# main.net
KiCad netlist of a schematic drawn in EAGLE
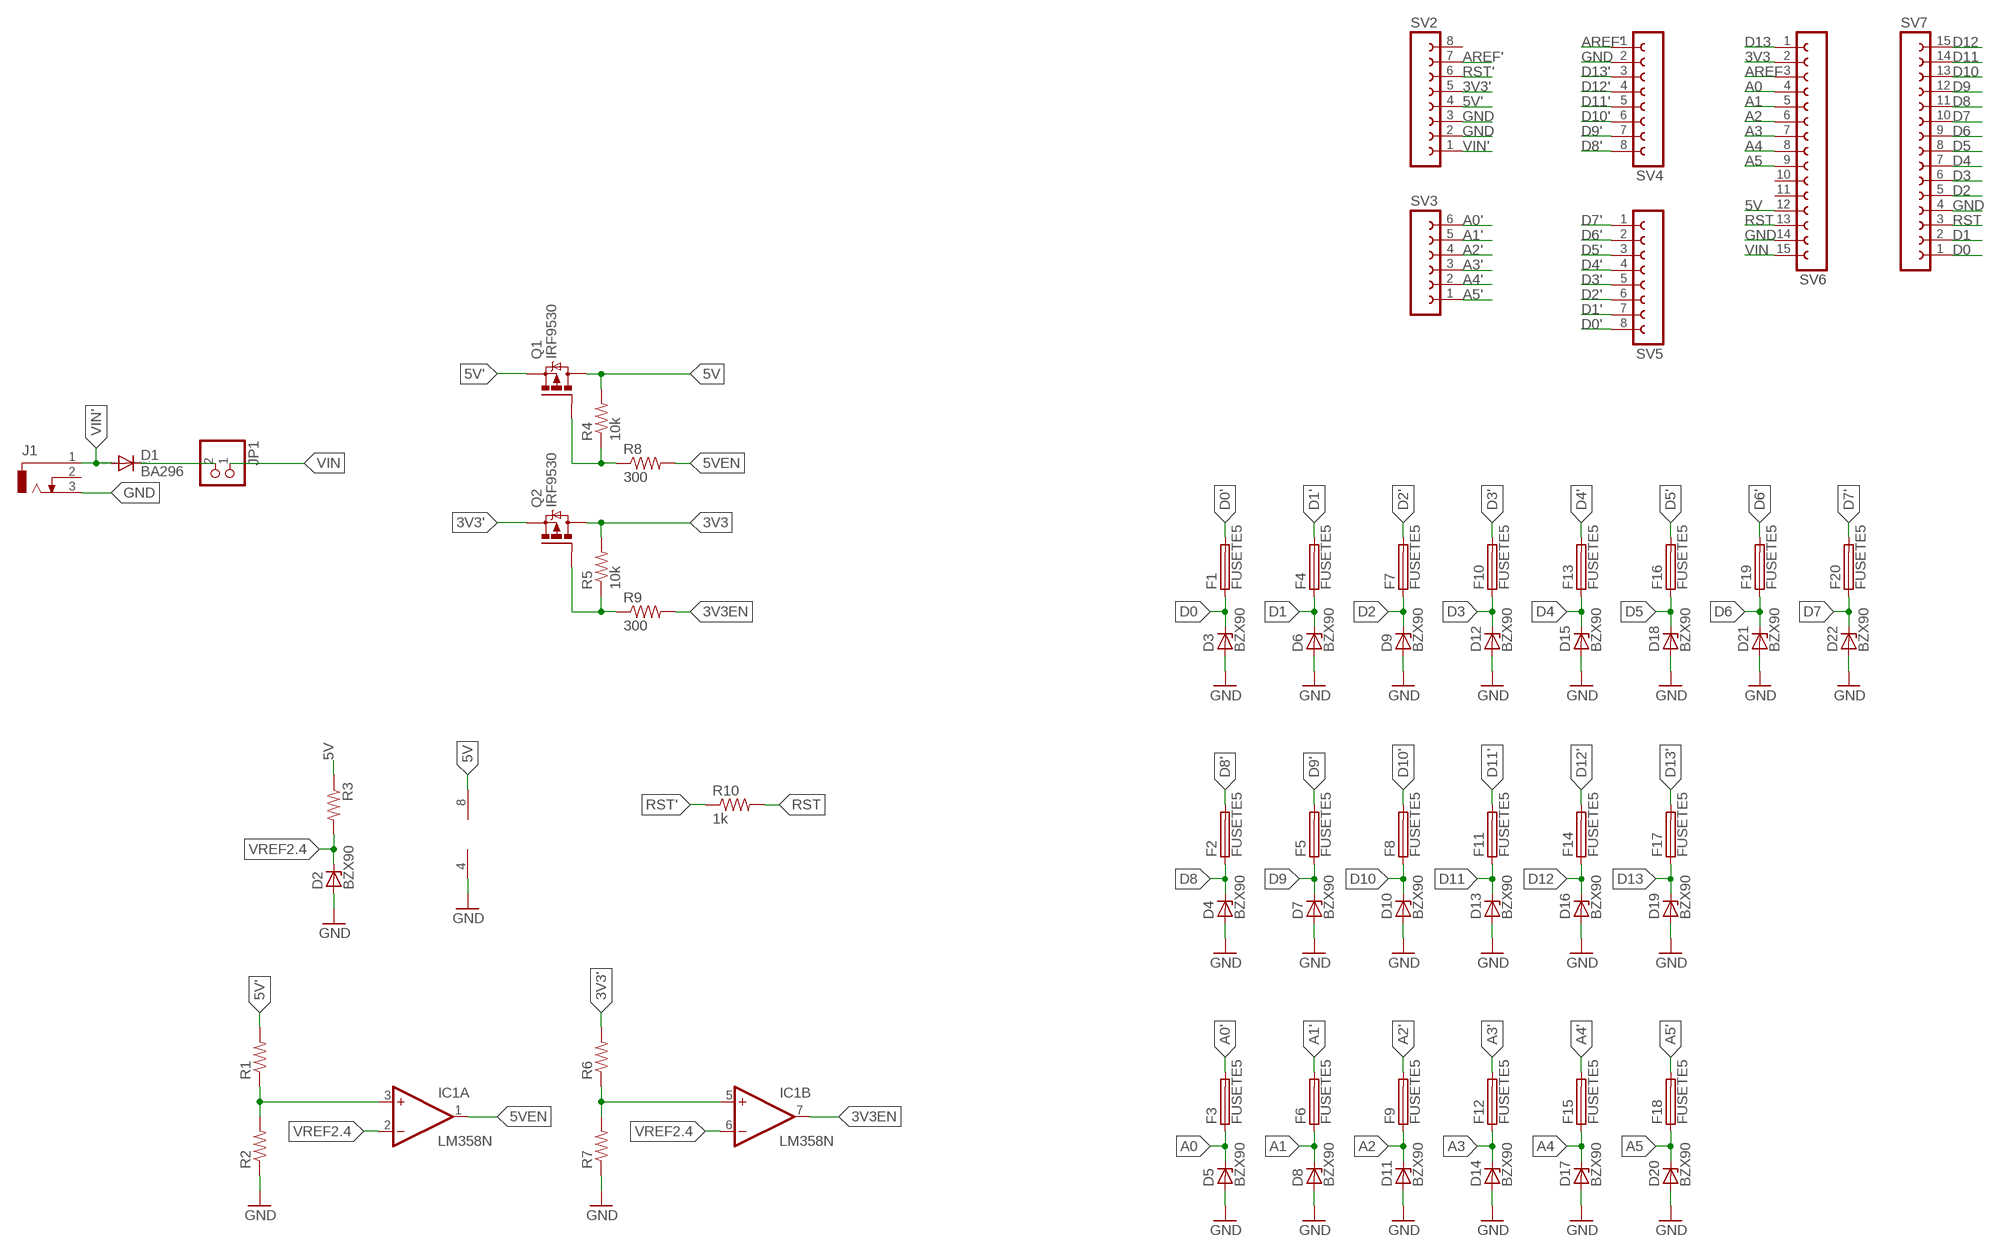
[diagram p0: schematic, sheet 1]

(export (version "E")
  (design (tool "Eeschema 10.0.6"))
  (components
    (comp (ref "D1")
      (value "BA296")
      (footprint "eagle-import:P2-15")
      (libsource (lib "eagle-import") (part "BA296"))
    )
    (comp (ref "D2")
      (value "BZX90")
      (footprint "eagle-import:DO34Z7")
      (libsource (lib "eagle-import") (part "BZX90"))
    )
    (comp (ref "D3")
      (value "BZX90")
      (footprint "eagle-import:DO34Z7")
      (libsource (lib "eagle-import") (part "BZX90"))
    )
    (comp (ref "D4")
      (value "BZX90")
      (footprint "eagle-import:DO34Z7")
      (libsource (lib "eagle-import") (part "BZX90"))
    )
    (comp (ref "D5")
      (value "BZX90")
      (footprint "eagle-import:DO34Z7")
      (libsource (lib "eagle-import") (part "BZX90"))
    )
    (comp (ref "D6")
      (value "BZX90")
      (footprint "eagle-import:DO34Z7")
      (libsource (lib "eagle-import") (part "BZX90"))
    )
    (comp (ref "D7")
      (value "BZX90")
      (footprint "eagle-import:DO34Z7")
      (libsource (lib "eagle-import") (part "BZX90"))
    )
    (comp (ref "D8")
      (value "BZX90")
      (footprint "eagle-import:DO34Z7")
      (libsource (lib "eagle-import") (part "BZX90"))
    )
    (comp (ref "D9")
      (value "BZX90")
      (footprint "eagle-import:DO34Z7")
      (libsource (lib "eagle-import") (part "BZX90"))
    )
    (comp (ref "D10")
      (value "BZX90")
      (footprint "eagle-import:DO34Z7")
      (libsource (lib "eagle-import") (part "BZX90"))
    )
    (comp (ref "D11")
      (value "BZX90")
      (footprint "eagle-import:DO34Z7")
      (libsource (lib "eagle-import") (part "BZX90"))
    )
    (comp (ref "D12")
      (value "BZX90")
      (footprint "eagle-import:DO34Z7")
      (libsource (lib "eagle-import") (part "BZX90"))
    )
    (comp (ref "D13")
      (value "BZX90")
      (footprint "eagle-import:DO34Z7")
      (libsource (lib "eagle-import") (part "BZX90"))
    )
    (comp (ref "D14")
      (value "BZX90")
      (footprint "eagle-import:DO34Z7")
      (libsource (lib "eagle-import") (part "BZX90"))
    )
    (comp (ref "D15")
      (value "BZX90")
      (footprint "eagle-import:DO34Z7")
      (libsource (lib "eagle-import") (part "BZX90"))
    )
    (comp (ref "D16")
      (value "BZX90")
      (footprint "eagle-import:DO34Z7")
      (libsource (lib "eagle-import") (part "BZX90"))
    )
    (comp (ref "D17")
      (value "BZX90")
      (footprint "eagle-import:DO34Z7")
      (libsource (lib "eagle-import") (part "BZX90"))
    )
    (comp (ref "D18")
      (value "BZX90")
      (footprint "eagle-import:DO34Z7")
      (libsource (lib "eagle-import") (part "BZX90"))
    )
    (comp (ref "D19")
      (value "BZX90")
      (footprint "eagle-import:DO34Z7")
      (libsource (lib "eagle-import") (part "BZX90"))
    )
    (comp (ref "D20")
      (value "BZX90")
      (footprint "eagle-import:DO34Z7")
      (libsource (lib "eagle-import") (part "BZX90"))
    )
    (comp (ref "D21")
      (value "BZX90")
      (footprint "eagle-import:DO34Z7")
      (libsource (lib "eagle-import") (part "BZX90"))
    )
    (comp (ref "D22")
      (value "BZX90")
      (footprint "eagle-import:DO34Z7")
      (libsource (lib "eagle-import") (part "BZX90"))
    )
    (comp (ref "F1")
      (value "FUSETE5")
      (footprint "eagle-import:TE5")
      (libsource (lib "eagle-import") (part "FUSETE5"))
    )
    (comp (ref "F2")
      (value "FUSETE5")
      (footprint "eagle-import:TE5")
      (libsource (lib "eagle-import") (part "FUSETE5"))
    )
    (comp (ref "F3")
      (value "FUSETE5")
      (footprint "eagle-import:TE5")
      (libsource (lib "eagle-import") (part "FUSETE5"))
    )
    (comp (ref "F4")
      (value "FUSETE5")
      (footprint "eagle-import:TE5")
      (libsource (lib "eagle-import") (part "FUSETE5"))
    )
    (comp (ref "F5")
      (value "FUSETE5")
      (footprint "eagle-import:TE5")
      (libsource (lib "eagle-import") (part "FUSETE5"))
    )
    (comp (ref "F6")
      (value "FUSETE5")
      (footprint "eagle-import:TE5")
      (libsource (lib "eagle-import") (part "FUSETE5"))
    )
    (comp (ref "F7")
      (value "FUSETE5")
      (footprint "eagle-import:TE5")
      (libsource (lib "eagle-import") (part "FUSETE5"))
    )
    (comp (ref "F8")
      (value "FUSETE5")
      (footprint "eagle-import:TE5")
      (libsource (lib "eagle-import") (part "FUSETE5"))
    )
    (comp (ref "F9")
      (value "FUSETE5")
      (footprint "eagle-import:TE5")
      (libsource (lib "eagle-import") (part "FUSETE5"))
    )
    (comp (ref "F10")
      (value "FUSETE5")
      (footprint "eagle-import:TE5")
      (libsource (lib "eagle-import") (part "FUSETE5"))
    )
    (comp (ref "F11")
      (value "FUSETE5")
      (footprint "eagle-import:TE5")
      (libsource (lib "eagle-import") (part "FUSETE5"))
    )
    (comp (ref "F12")
      (value "FUSETE5")
      (footprint "eagle-import:TE5")
      (libsource (lib "eagle-import") (part "FUSETE5"))
    )
    (comp (ref "F13")
      (value "FUSETE5")
      (footprint "eagle-import:TE5")
      (libsource (lib "eagle-import") (part "FUSETE5"))
    )
    (comp (ref "F14")
      (value "FUSETE5")
      (footprint "eagle-import:TE5")
      (libsource (lib "eagle-import") (part "FUSETE5"))
    )
    (comp (ref "F15")
      (value "FUSETE5")
      (footprint "eagle-import:TE5")
      (libsource (lib "eagle-import") (part "FUSETE5"))
    )
    (comp (ref "F16")
      (value "FUSETE5")
      (footprint "eagle-import:TE5")
      (libsource (lib "eagle-import") (part "FUSETE5"))
    )
    (comp (ref "F17")
      (value "FUSETE5")
      (footprint "eagle-import:TE5")
      (libsource (lib "eagle-import") (part "FUSETE5"))
    )
    (comp (ref "F18")
      (value "FUSETE5")
      (footprint "eagle-import:TE5")
      (libsource (lib "eagle-import") (part "FUSETE5"))
    )
    (comp (ref "F19")
      (value "FUSETE5")
      (footprint "eagle-import:TE5")
      (libsource (lib "eagle-import") (part "FUSETE5"))
    )
    (comp (ref "F20")
      (value "FUSETE5")
      (footprint "eagle-import:TE5")
      (libsource (lib "eagle-import") (part "FUSETE5"))
    )
    (comp (ref "IC1")
      (value "LM358N")
      (footprint "eagle-import:DIL08")
      (libsource (lib "eagle-import") (part "LM358N"))
    )
    (comp (ref "J1")
      (value "DCJ0303")
      (footprint "eagle-import:DCJ0303")
      (libsource (lib "eagle-import") (part "DCJ0303"))
    )
    (comp (ref "JP1")
      (value "PINHD-1X2")
      (footprint "eagle-import:1X02")
      (libsource (lib "eagle-import") (part "PINHD-1X2"))
    )
    (comp (ref "Q1")
      (value "IRF9530")
      (footprint "eagle-import:TO220BV")
      (libsource (lib "eagle-import") (part "IRF9530"))
    )
    (comp (ref "Q2")
      (value "IRF9530")
      (footprint "eagle-import:TO220BV")
      (libsource (lib "eagle-import") (part "IRF9530"))
    )
    (comp (ref "R1")
      (value "R-US_0204/7")
      (footprint "eagle-import:0204_7")
      (libsource (lib "eagle-import") (part "R-US_0204/7"))
    )
    (comp (ref "R2")
      (value "R-US_0204/7")
      (footprint "eagle-import:0204_7")
      (libsource (lib "eagle-import") (part "R-US_0204/7"))
    )
    (comp (ref "R3")
      (value "R-US_0204/7")
      (footprint "eagle-import:0204_7")
      (libsource (lib "eagle-import") (part "R-US_0204/7"))
    )
    (comp (ref "R4")
      (value "10k")
      (footprint "eagle-import:0204_7")
      (libsource (lib "eagle-import") (part "R-US_0204/7"))
    )
    (comp (ref "R5")
      (value "10k")
      (footprint "eagle-import:0204_7")
      (libsource (lib "eagle-import") (part "R-US_0204/7"))
    )
    (comp (ref "R6")
      (value "R-US_0204/7")
      (footprint "eagle-import:0204_7")
      (libsource (lib "eagle-import") (part "R-US_0204/7"))
    )
    (comp (ref "R7")
      (value "R-US_0204/7")
      (footprint "eagle-import:0204_7")
      (libsource (lib "eagle-import") (part "R-US_0204/7"))
    )
    (comp (ref "R8")
      (value "300")
      (footprint "eagle-import:0204_7")
      (libsource (lib "eagle-import") (part "R-US_0204/7"))
    )
    (comp (ref "R9")
      (value "300")
      (footprint "eagle-import:0204_7")
      (libsource (lib "eagle-import") (part "R-US_0204/7"))
    )
    (comp (ref "R10")
      (value "1k")
      (footprint "eagle-import:0204_7")
      (libsource (lib "eagle-import") (part "R-US_0204/7"))
    )
    (comp (ref "SV2")
      (value "FE08-1")
      (footprint "eagle-import:FE08")
      (libsource (lib "eagle-import") (part "FE08-1"))
    )
    (comp (ref "SV3")
      (value "FE06-1")
      (footprint "eagle-import:FE06")
      (libsource (lib "eagle-import") (part "FE06-1"))
    )
    (comp (ref "SV4")
      (value "FE08-1")
      (footprint "eagle-import:FE08")
      (libsource (lib "eagle-import") (part "FE08-1"))
    )
    (comp (ref "SV5")
      (value "FE08-1")
      (footprint "eagle-import:FE08")
      (libsource (lib "eagle-import") (part "FE08-1"))
    )
    (comp (ref "SV6")
      (value "FE15-1")
      (footprint "eagle-import:FE15")
      (libsource (lib "eagle-import") (part "FE15-1"))
    )
    (comp (ref "SV7")
      (value "FE15-1")
      (footprint "eagle-import:FE15")
      (libsource (lib "eagle-import") (part "FE15-1"))
    )
  )
  (nets
    (net (code "1") (name "/AREF") (class "Default")
      (node (ref "SV6") (pin "3") (pinfunction "3_3") (pintype "passive"))
    )
    (net (code "2") (name "/AREF'") (class "Default")
      (node (ref "SV2") (pin "7") (pinfunction "7_7") (pintype "passive"))
      (node (ref "SV4") (pin "1") (pinfunction "1_1") (pintype "passive"))
    )
    (net (code "3") (name "3V3") (class "Default")
      (node (ref "Q2") (pin "D") (pinfunction "D_D") (pintype "passive"))
      (node (ref "R5") (pin "2") (pinfunction "2_2") (pintype "passive"))
      (node (ref "SV6") (pin "2") (pinfunction "2_2") (pintype "passive"))
    )
    (net (code "4") (name "3V3'") (class "Default")
      (node (ref "Q2") (pin "S") (pinfunction "S_S") (pintype "passive"))
      (node (ref "R6") (pin "2") (pinfunction "2_2") (pintype "passive"))
      (node (ref "SV2") (pin "5") (pinfunction "5_5") (pintype "passive"))
    )
    (net (code "5") (name "3V3EN") (class "Default")
      (node (ref "IC1") (pin "7") (pinfunction "OUT_7") (pintype "output"))
      (node (ref "R9") (pin "2") (pinfunction "2_2") (pintype "passive"))
    )
    (net (code "6") (name "5V") (class "Default")
      (node (ref "IC1") (pin "8") (pinfunction "V+_8") (pintype "power_in"))
      (node (ref "Q1") (pin "D") (pinfunction "D_D") (pintype "passive"))
      (node (ref "R3") (pin "1") (pinfunction "1_1") (pintype "passive"))
      (node (ref "R4") (pin "2") (pinfunction "2_2") (pintype "passive"))
      (node (ref "SV6") (pin "12") (pinfunction "12_12") (pintype "passive"))
    )
    (net (code "7") (name "5V'") (class "Default")
      (node (ref "Q1") (pin "S") (pinfunction "S_S") (pintype "passive"))
      (node (ref "R1") (pin "2") (pinfunction "2_2") (pintype "passive"))
      (node (ref "SV2") (pin "4") (pinfunction "4_4") (pintype "passive"))
    )
    (net (code "8") (name "5VEN") (class "Default")
      (node (ref "IC1") (pin "1") (pinfunction "OUT_1") (pintype "output"))
      (node (ref "R8") (pin "2") (pinfunction "2_2") (pintype "passive"))
    )
    (net (code "9") (name "A0") (class "Default")
      (node (ref "D5") (pin "C") (pinfunction "C_C") (pintype "passive"))
      (node (ref "F3") (pin "1") (pinfunction "1_1") (pintype "passive"))
      (node (ref "SV6") (pin "4") (pinfunction "4_4") (pintype "passive"))
    )
    (net (code "10") (name "A0'") (class "Default")
      (node (ref "F3") (pin "2") (pinfunction "2_2") (pintype "passive"))
      (node (ref "SV3") (pin "6") (pinfunction "6_6") (pintype "passive"))
    )
    (net (code "11") (name "A1") (class "Default")
      (node (ref "D8") (pin "C") (pinfunction "C_C") (pintype "passive"))
      (node (ref "F6") (pin "1") (pinfunction "1_1") (pintype "passive"))
      (node (ref "SV6") (pin "5") (pinfunction "5_5") (pintype "passive"))
    )
    (net (code "12") (name "A1'") (class "Default")
      (node (ref "F6") (pin "2") (pinfunction "2_2") (pintype "passive"))
      (node (ref "SV3") (pin "5") (pinfunction "5_5") (pintype "passive"))
    )
    (net (code "13") (name "A2") (class "Default")
      (node (ref "D11") (pin "C") (pinfunction "C_C") (pintype "passive"))
      (node (ref "F9") (pin "1") (pinfunction "1_1") (pintype "passive"))
      (node (ref "SV6") (pin "6") (pinfunction "6_6") (pintype "passive"))
    )
    (net (code "14") (name "A2'") (class "Default")
      (node (ref "F9") (pin "2") (pinfunction "2_2") (pintype "passive"))
      (node (ref "SV3") (pin "4") (pinfunction "4_4") (pintype "passive"))
    )
    (net (code "15") (name "A3") (class "Default")
      (node (ref "D14") (pin "C") (pinfunction "C_C") (pintype "passive"))
      (node (ref "F12") (pin "1") (pinfunction "1_1") (pintype "passive"))
      (node (ref "SV6") (pin "7") (pinfunction "7_7") (pintype "passive"))
    )
    (net (code "16") (name "A3'") (class "Default")
      (node (ref "F12") (pin "2") (pinfunction "2_2") (pintype "passive"))
      (node (ref "SV3") (pin "3") (pinfunction "3_3") (pintype "passive"))
    )
    (net (code "17") (name "A4") (class "Default")
      (node (ref "D17") (pin "C") (pinfunction "C_C") (pintype "passive"))
      (node (ref "F15") (pin "1") (pinfunction "1_1") (pintype "passive"))
      (node (ref "SV6") (pin "8") (pinfunction "8_8") (pintype "passive"))
    )
    (net (code "18") (name "A4'") (class "Default")
      (node (ref "F15") (pin "2") (pinfunction "2_2") (pintype "passive"))
      (node (ref "SV3") (pin "2") (pinfunction "2_2") (pintype "passive"))
    )
    (net (code "19") (name "A5") (class "Default")
      (node (ref "D20") (pin "C") (pinfunction "C_C") (pintype "passive"))
      (node (ref "F18") (pin "1") (pinfunction "1_1") (pintype "passive"))
      (node (ref "SV6") (pin "9") (pinfunction "9_9") (pintype "passive"))
    )
    (net (code "20") (name "A5'") (class "Default")
      (node (ref "F18") (pin "2") (pinfunction "2_2") (pintype "passive"))
      (node (ref "SV3") (pin "1") (pinfunction "1_1") (pintype "passive"))
    )
    (net (code "21") (name "D0") (class "Default")
      (node (ref "D3") (pin "C") (pinfunction "C_C") (pintype "passive"))
      (node (ref "F1") (pin "1") (pinfunction "1_1") (pintype "passive"))
      (node (ref "SV7") (pin "1") (pinfunction "1_1") (pintype "passive"))
    )
    (net (code "22") (name "D0'") (class "Default")
      (node (ref "F1") (pin "2") (pinfunction "2_2") (pintype "passive"))
      (node (ref "SV5") (pin "8") (pinfunction "8_8") (pintype "passive"))
    )
    (net (code "23") (name "D1") (class "Default")
      (node (ref "D6") (pin "C") (pinfunction "C_C") (pintype "passive"))
      (node (ref "F4") (pin "1") (pinfunction "1_1") (pintype "passive"))
      (node (ref "SV7") (pin "2") (pinfunction "2_2") (pintype "passive"))
    )
    (net (code "24") (name "D1'") (class "Default")
      (node (ref "F4") (pin "2") (pinfunction "2_2") (pintype "passive"))
      (node (ref "SV5") (pin "7") (pinfunction "7_7") (pintype "passive"))
    )
    (net (code "25") (name "D2") (class "Default")
      (node (ref "D9") (pin "C") (pinfunction "C_C") (pintype "passive"))
      (node (ref "F7") (pin "1") (pinfunction "1_1") (pintype "passive"))
      (node (ref "SV7") (pin "5") (pinfunction "5_5") (pintype "passive"))
    )
    (net (code "26") (name "D2'") (class "Default")
      (node (ref "F7") (pin "2") (pinfunction "2_2") (pintype "passive"))
      (node (ref "SV5") (pin "6") (pinfunction "6_6") (pintype "passive"))
    )
    (net (code "27") (name "D3") (class "Default")
      (node (ref "D12") (pin "C") (pinfunction "C_C") (pintype "passive"))
      (node (ref "F10") (pin "1") (pinfunction "1_1") (pintype "passive"))
      (node (ref "SV7") (pin "6") (pinfunction "6_6") (pintype "passive"))
    )
    (net (code "28") (name "D3'") (class "Default")
      (node (ref "F10") (pin "2") (pinfunction "2_2") (pintype "passive"))
      (node (ref "SV5") (pin "5") (pinfunction "5_5") (pintype "passive"))
    )
    (net (code "29") (name "D4") (class "Default")
      (node (ref "D15") (pin "C") (pinfunction "C_C") (pintype "passive"))
      (node (ref "F13") (pin "1") (pinfunction "1_1") (pintype "passive"))
      (node (ref "SV7") (pin "7") (pinfunction "7_7") (pintype "passive"))
    )
    (net (code "30") (name "D4'") (class "Default")
      (node (ref "F13") (pin "2") (pinfunction "2_2") (pintype "passive"))
      (node (ref "SV5") (pin "4") (pinfunction "4_4") (pintype "passive"))
    )
    (net (code "31") (name "D5") (class "Default")
      (node (ref "D18") (pin "C") (pinfunction "C_C") (pintype "passive"))
      (node (ref "F16") (pin "1") (pinfunction "1_1") (pintype "passive"))
      (node (ref "SV7") (pin "8") (pinfunction "8_8") (pintype "passive"))
    )
    (net (code "32") (name "D5'") (class "Default")
      (node (ref "F16") (pin "2") (pinfunction "2_2") (pintype "passive"))
      (node (ref "SV5") (pin "3") (pinfunction "3_3") (pintype "passive"))
    )
    (net (code "33") (name "D6") (class "Default")
      (node (ref "D21") (pin "C") (pinfunction "C_C") (pintype "passive"))
      (node (ref "F19") (pin "1") (pinfunction "1_1") (pintype "passive"))
      (node (ref "SV7") (pin "9") (pinfunction "9_9") (pintype "passive"))
    )
    (net (code "34") (name "D6'") (class "Default")
      (node (ref "F19") (pin "2") (pinfunction "2_2") (pintype "passive"))
      (node (ref "SV5") (pin "2") (pinfunction "2_2") (pintype "passive"))
    )
    (net (code "35") (name "D7") (class "Default")
      (node (ref "D22") (pin "C") (pinfunction "C_C") (pintype "passive"))
      (node (ref "F20") (pin "1") (pinfunction "1_1") (pintype "passive"))
      (node (ref "SV7") (pin "10") (pinfunction "10_10") (pintype "passive"))
    )
    (net (code "36") (name "D7'") (class "Default")
      (node (ref "F20") (pin "2") (pinfunction "2_2") (pintype "passive"))
      (node (ref "SV5") (pin "1") (pinfunction "1_1") (pintype "passive"))
    )
    (net (code "37") (name "D8") (class "Default")
      (node (ref "D4") (pin "C") (pinfunction "C_C") (pintype "passive"))
      (node (ref "F2") (pin "1") (pinfunction "1_1") (pintype "passive"))
      (node (ref "SV7") (pin "11") (pinfunction "11_11") (pintype "passive"))
    )
    (net (code "38") (name "D8'") (class "Default")
      (node (ref "F2") (pin "2") (pinfunction "2_2") (pintype "passive"))
      (node (ref "SV4") (pin "8") (pinfunction "8_8") (pintype "passive"))
    )
    (net (code "39") (name "D9") (class "Default")
      (node (ref "D7") (pin "C") (pinfunction "C_C") (pintype "passive"))
      (node (ref "F5") (pin "1") (pinfunction "1_1") (pintype "passive"))
      (node (ref "SV7") (pin "12") (pinfunction "12_12") (pintype "passive"))
    )
    (net (code "40") (name "D9'") (class "Default")
      (node (ref "F5") (pin "2") (pinfunction "2_2") (pintype "passive"))
      (node (ref "SV4") (pin "7") (pinfunction "7_7") (pintype "passive"))
    )
    (net (code "41") (name "D10") (class "Default")
      (node (ref "D10") (pin "C") (pinfunction "C_C") (pintype "passive"))
      (node (ref "F8") (pin "1") (pinfunction "1_1") (pintype "passive"))
      (node (ref "SV7") (pin "13") (pinfunction "13_13") (pintype "passive"))
    )
    (net (code "42") (name "D10'") (class "Default")
      (node (ref "F8") (pin "2") (pinfunction "2_2") (pintype "passive"))
      (node (ref "SV4") (pin "6") (pinfunction "6_6") (pintype "passive"))
    )
    (net (code "43") (name "D11") (class "Default")
      (node (ref "D13") (pin "C") (pinfunction "C_C") (pintype "passive"))
      (node (ref "F11") (pin "1") (pinfunction "1_1") (pintype "passive"))
      (node (ref "SV7") (pin "14") (pinfunction "14_14") (pintype "passive"))
    )
    (net (code "44") (name "D11'") (class "Default")
      (node (ref "F11") (pin "2") (pinfunction "2_2") (pintype "passive"))
      (node (ref "SV4") (pin "5") (pinfunction "5_5") (pintype "passive"))
    )
    (net (code "45") (name "D12") (class "Default")
      (node (ref "D16") (pin "C") (pinfunction "C_C") (pintype "passive"))
      (node (ref "F14") (pin "1") (pinfunction "1_1") (pintype "passive"))
      (node (ref "SV7") (pin "15") (pinfunction "15_15") (pintype "passive"))
    )
    (net (code "46") (name "D12'") (class "Default")
      (node (ref "F14") (pin "2") (pinfunction "2_2") (pintype "passive"))
      (node (ref "SV4") (pin "4") (pinfunction "4_4") (pintype "passive"))
    )
    (net (code "47") (name "D13") (class "Default")
      (node (ref "D19") (pin "C") (pinfunction "C_C") (pintype "passive"))
      (node (ref "F17") (pin "1") (pinfunction "1_1") (pintype "passive"))
      (node (ref "SV6") (pin "1") (pinfunction "1_1") (pintype "passive"))
    )
    (net (code "48") (name "D13'") (class "Default")
      (node (ref "F17") (pin "2") (pinfunction "2_2") (pintype "passive"))
      (node (ref "SV4") (pin "3") (pinfunction "3_3") (pintype "passive"))
    )
    (net (code "49") (name "GND") (class "Default")
      (node (ref "D10") (pin "A") (pinfunction "A_A") (pintype "passive"))
      (node (ref "D11") (pin "A") (pinfunction "A_A") (pintype "passive"))
      (node (ref "D12") (pin "A") (pinfunction "A_A") (pintype "passive"))
      (node (ref "D13") (pin "A") (pinfunction "A_A") (pintype "passive"))
      (node (ref "D14") (pin "A") (pinfunction "A_A") (pintype "passive"))
      (node (ref "D15") (pin "A") (pinfunction "A_A") (pintype "passive"))
      (node (ref "D16") (pin "A") (pinfunction "A_A") (pintype "passive"))
      (node (ref "D17") (pin "A") (pinfunction "A_A") (pintype "passive"))
      (node (ref "D18") (pin "A") (pinfunction "A_A") (pintype "passive"))
      (node (ref "D19") (pin "A") (pinfunction "A_A") (pintype "passive"))
      (node (ref "D2") (pin "A") (pinfunction "A_A") (pintype "passive"))
      (node (ref "D20") (pin "A") (pinfunction "A_A") (pintype "passive"))
      (node (ref "D21") (pin "A") (pinfunction "A_A") (pintype "passive"))
      (node (ref "D22") (pin "A") (pinfunction "A_A") (pintype "passive"))
      (node (ref "D3") (pin "A") (pinfunction "A_A") (pintype "passive"))
      (node (ref "D4") (pin "A") (pinfunction "A_A") (pintype "passive"))
      (node (ref "D5") (pin "A") (pinfunction "A_A") (pintype "passive"))
      (node (ref "D6") (pin "A") (pinfunction "A_A") (pintype "passive"))
      (node (ref "D7") (pin "A") (pinfunction "A_A") (pintype "passive"))
      (node (ref "D8") (pin "A") (pinfunction "A_A") (pintype "passive"))
      (node (ref "D9") (pin "A") (pinfunction "A_A") (pintype "passive"))
      (node (ref "IC1") (pin "4") (pinfunction "V-_4") (pintype "power_in"))
      (node (ref "J1") (pin "3") (pinfunction "3_3") (pintype "passive"))
      (node (ref "R2") (pin "1") (pinfunction "1_1") (pintype "passive"))
      (node (ref "R7") (pin "1") (pinfunction "1_1") (pintype "passive"))
      (node (ref "SV2") (pin "2") (pinfunction "2_2") (pintype "passive"))
      (node (ref "SV2") (pin "3") (pinfunction "3_3") (pintype "passive"))
      (node (ref "SV4") (pin "2") (pinfunction "2_2") (pintype "passive"))
      (node (ref "SV6") (pin "14") (pinfunction "14_14") (pintype "passive"))
      (node (ref "SV7") (pin "4") (pinfunction "4_4") (pintype "passive"))
    )
    (net (code "50") (name "Net-(D1-PadC)") (class "Default")
      (node (ref "D1") (pin "C") (pinfunction "C_C") (pintype "passive"))
      (node (ref "JP1") (pin "2") (pinfunction "2_2") (pintype "passive"))
    )
    (net (code "51") (name "Net-(IC1A-+IN)") (class "Default")
      (node (ref "IC1") (pin "3") (pinfunction "+IN_3") (pintype "input"))
      (node (ref "R1") (pin "1") (pinfunction "1_1") (pintype "passive"))
      (node (ref "R2") (pin "2") (pinfunction "2_2") (pintype "passive"))
    )
    (net (code "52") (name "Net-(IC1B-+IN)") (class "Default")
      (node (ref "IC1") (pin "5") (pinfunction "+IN_5") (pintype "input"))
      (node (ref "R6") (pin "1") (pinfunction "1_1") (pintype "passive"))
      (node (ref "R7") (pin "2") (pinfunction "2_2") (pintype "passive"))
    )
    (net (code "53") (name "Net-(Q1-PadG)") (class "Default")
      (node (ref "Q1") (pin "G") (pinfunction "G_G") (pintype "passive"))
      (node (ref "R4") (pin "1") (pinfunction "1_1") (pintype "passive"))
      (node (ref "R8") (pin "1") (pinfunction "1_1") (pintype "passive"))
    )
    (net (code "54") (name "Net-(Q2-PadG)") (class "Default")
      (node (ref "Q2") (pin "G") (pinfunction "G_G") (pintype "passive"))
      (node (ref "R5") (pin "1") (pinfunction "1_1") (pintype "passive"))
      (node (ref "R9") (pin "1") (pinfunction "1_1") (pintype "passive"))
    )
    (net (code "55") (name "RST") (class "Default")
      (node (ref "R10") (pin "2") (pinfunction "2_2") (pintype "passive"))
      (node (ref "SV6") (pin "13") (pinfunction "13_13") (pintype "passive"))
      (node (ref "SV7") (pin "3") (pinfunction "3_3") (pintype "passive"))
    )
    (net (code "56") (name "RST'") (class "Default")
      (node (ref "R10") (pin "1") (pinfunction "1_1") (pintype "passive"))
      (node (ref "SV2") (pin "6") (pinfunction "6_6") (pintype "passive"))
    )
    (net (code "57") (name "VIN") (class "Default")
      (node (ref "JP1") (pin "1") (pinfunction "1_1") (pintype "passive"))
      (node (ref "SV6") (pin "15") (pinfunction "15_15") (pintype "passive"))
    )
    (net (code "58") (name "VIN'") (class "Default")
      (node (ref "D1") (pin "A") (pinfunction "A_A") (pintype "passive"))
      (node (ref "J1") (pin "1") (pinfunction "1_1") (pintype "passive"))
      (node (ref "SV2") (pin "1") (pinfunction "1_1") (pintype "passive"))
    )
    (net (code "59") (name "VREF2.4") (class "Default")
      (node (ref "D2") (pin "C") (pinfunction "C_C") (pintype "passive"))
      (node (ref "IC1") (pin "2") (pinfunction "-IN_2") (pintype "input"))
      (node (ref "IC1") (pin "6") (pinfunction "-IN_6") (pintype "input"))
      (node (ref "R3") (pin "2") (pinfunction "2_2") (pintype "passive"))
    )
    (net (code "60") (name "unconnected-(J1-Pad2)") (class "Default")
      (node (ref "J1") (pin "2") (pinfunction "2_2") (pintype "passive"))
    )
    (net (code "61") (name "unconnected-(SV2-Pad8)") (class "Default")
      (node (ref "SV2") (pin "8") (pinfunction "8_8") (pintype "passive"))
    )
    (net (code "62") (name "unconnected-(SV6-Pad10)") (class "Default")
      (node (ref "SV6") (pin "10") (pinfunction "10_10") (pintype "passive"))
    )
    (net (code "63") (name "unconnected-(SV6-Pad11)") (class "Default")
      (node (ref "SV6") (pin "11") (pinfunction "11_11") (pintype "passive"))
    )
  )
)
